# AnalogOutput.net
KiCad netlist of a schematic drawn in Altium Designer
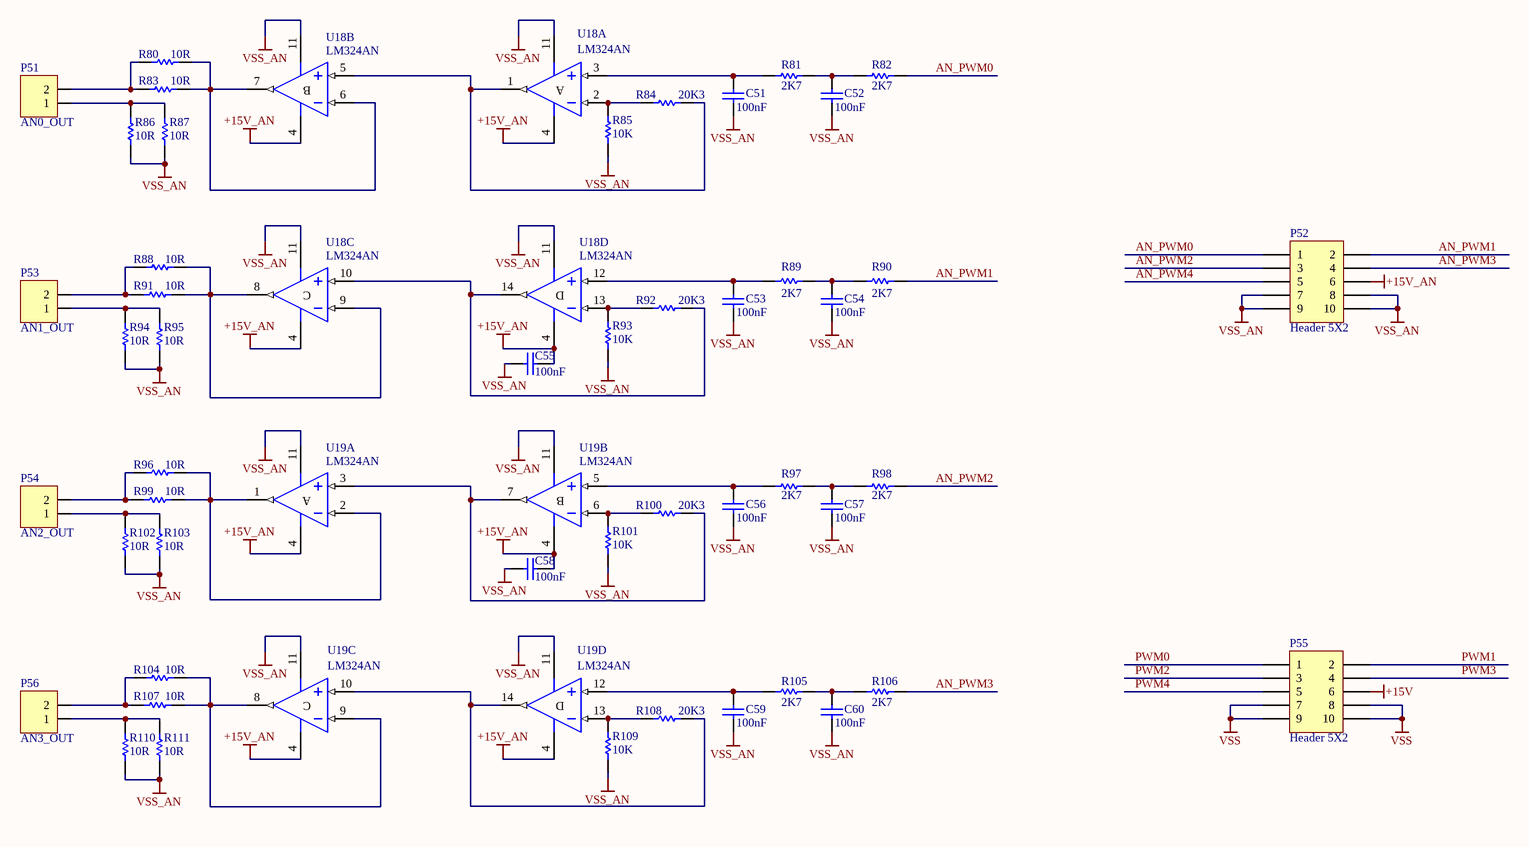
[diagram p0: AnalogOutput.SchDoc]

(export (version "E")
  (design (tool "Eeschema 10.0.6"))
  (components
    (comp (ref "C51")
      (value "100nF")
      (footprint "1206")
      (description "Ceramic Chip Capacitor - Standard")
      (fields (field (name "PUBLISHER") "Altium Limited"))
      (libsource (lib "KEMET Chip Capacitor") (part "C1206"))
    )
    (comp (ref "C52")
      (value "100nF")
      (footprint "1206")
      (description "Ceramic Chip Capacitor - Standard")
      (fields (field (name "PUBLISHER") "Altium Limited"))
      (libsource (lib "KEMET Chip Capacitor") (part "C1206"))
    )
    (comp (ref "C53")
      (value "100nF")
      (footprint "1206")
      (description "Ceramic Chip Capacitor - Standard")
      (fields (field (name "PUBLISHER") "Altium Limited"))
      (libsource (lib "KEMET Chip Capacitor") (part "C1206"))
    )
    (comp (ref "C54")
      (value "100nF")
      (footprint "1206")
      (description "Ceramic Chip Capacitor - Standard")
      (fields (field (name "PUBLISHER") "Altium Limited"))
      (libsource (lib "KEMET Chip Capacitor") (part "C1206"))
    )
    (comp (ref "C55")
      (value "100nF")
      (footprint "1206")
      (description "Ceramic Chip Capacitor - Standard")
      (fields (field (name "PUBLISHER") "Altium Limited"))
      (libsource (lib "KEMET Chip Capacitor") (part "C1206"))
    )
    (comp (ref "C56")
      (value "100nF")
      (footprint "1206")
      (description "Ceramic Chip Capacitor - Standard")
      (fields (field (name "PUBLISHER") "Altium Limited"))
      (libsource (lib "KEMET Chip Capacitor") (part "C1206"))
    )
    (comp (ref "C57")
      (value "100nF")
      (footprint "1206")
      (description "Ceramic Chip Capacitor - Standard")
      (fields (field (name "PUBLISHER") "Altium Limited"))
      (libsource (lib "KEMET Chip Capacitor") (part "C1206"))
    )
    (comp (ref "C58")
      (value "100nF")
      (footprint "1206")
      (description "Ceramic Chip Capacitor - Standard")
      (fields (field (name "PUBLISHER") "Altium Limited"))
      (libsource (lib "KEMET Chip Capacitor") (part "C1206"))
    )
    (comp (ref "C59")
      (value "100nF")
      (footprint "1206")
      (description "Ceramic Chip Capacitor - Standard")
      (fields (field (name "PUBLISHER") "Altium Limited"))
      (libsource (lib "KEMET Chip Capacitor") (part "C1206"))
    )
    (comp (ref "C60")
      (value "100nF")
      (footprint "1206")
      (description "Ceramic Chip Capacitor - Standard")
      (fields (field (name "PUBLISHER") "Altium Limited"))
      (libsource (lib "KEMET Chip Capacitor") (part "C1206"))
    )
    (comp (ref "P51")
      (value "AN0_OUT")
      (footprint "TERMINAL BLOK 2")
      (description "Terminal blok konektor 3,5 mm")
      (libsource (lib "ProjectLibrary") (part "TERMINAL BLOK 2"))
    )
    (comp (ref "P52")
      (value "Header 5X2")
      (footprint "HDR2X5")
      (description "Header, 5-Pin, Dual row")
      (fields (field (name "PUBLISHER") "Altium Limited"))
      (libsource (lib "Miscellaneous Connectors") (part "Header 5X2"))
    )
    (comp (ref "P53")
      (value "AN1_OUT")
      (footprint "TERMINAL BLOK 2")
      (description "Terminal blok konektor 3,5 mm")
      (libsource (lib "ProjectLibrary") (part "TERMINAL BLOK 2"))
    )
    (comp (ref "P54")
      (value "AN2_OUT")
      (footprint "TERMINAL BLOK 2")
      (description "Terminal blok konektor 3,5 mm")
      (libsource (lib "ProjectLibrary") (part "TERMINAL BLOK 2"))
    )
    (comp (ref "P55")
      (value "Header 5X2")
      (footprint "HDR2X5")
      (description "Header, 5-Pin, Dual row")
      (fields (field (name "PUBLISHER") "Altium Limited"))
      (libsource (lib "Miscellaneous Connectors") (part "Header 5X2"))
    )
    (comp (ref "P56")
      (value "AN3_OUT")
      (footprint "TERMINAL BLOK 2")
      (description "Terminal blok konektor 3,5 mm")
      (libsource (lib "ProjectLibrary") (part "TERMINAL BLOK 2"))
    )
    (comp (ref "R80")
      (value "10R")
      (footprint "ERA-0603")
      (fields (field (name "PUBLISHER") "Altium Limited"))
      (libsource (lib "Panasonic Resistor") (part "ERA3Y"))
    )
    (comp (ref "R81")
      (value "2K7")
      (footprint "ERA-0603")
      (fields (field (name "PUBLISHER") "Altium Limited"))
      (libsource (lib "Panasonic Resistor") (part "ERA3Y"))
    )
    (comp (ref "R82")
      (value "2K7")
      (footprint "ERA-0603")
      (fields (field (name "PUBLISHER") "Altium Limited"))
      (libsource (lib "Panasonic Resistor") (part "ERA3Y"))
    )
    (comp (ref "R83")
      (value "10R")
      (footprint "ERA-0603")
      (fields (field (name "PUBLISHER") "Altium Limited"))
      (libsource (lib "Panasonic Resistor") (part "ERA3Y"))
    )
    (comp (ref "R84")
      (value "20K3")
      (footprint "ERA-0603")
      (fields (field (name "PUBLISHER") "Altium Limited"))
      (libsource (lib "Panasonic Resistor") (part "ERA3Y"))
    )
    (comp (ref "R85")
      (value "10K")
      (footprint "ERA-0603")
      (fields (field (name "PUBLISHER") "Altium Limited"))
      (libsource (lib "Panasonic Resistor") (part "ERA3Y"))
    )
    (comp (ref "R86")
      (value "10R")
      (footprint "ERA-0603")
      (fields (field (name "PUBLISHER") "Altium Limited"))
      (libsource (lib "Panasonic Resistor") (part "ERA3Y"))
    )
    (comp (ref "R87")
      (value "10R")
      (footprint "ERA-0603")
      (fields (field (name "PUBLISHER") "Altium Limited"))
      (libsource (lib "Panasonic Resistor") (part "ERA3Y"))
    )
    (comp (ref "R88")
      (value "10R")
      (footprint "ERA-0603")
      (fields (field (name "PUBLISHER") "Altium Limited"))
      (libsource (lib "Panasonic Resistor") (part "ERA3Y"))
    )
    (comp (ref "R89")
      (value "2K7")
      (footprint "ERA-0603")
      (fields (field (name "PUBLISHER") "Altium Limited"))
      (libsource (lib "Panasonic Resistor") (part "ERA3Y"))
    )
    (comp (ref "R90")
      (value "2K7")
      (footprint "ERA-0603")
      (fields (field (name "PUBLISHER") "Altium Limited"))
      (libsource (lib "Panasonic Resistor") (part "ERA3Y"))
    )
    (comp (ref "R91")
      (value "10R")
      (footprint "ERA-0603")
      (fields (field (name "PUBLISHER") "Altium Limited"))
      (libsource (lib "Panasonic Resistor") (part "ERA3Y"))
    )
    (comp (ref "R92")
      (value "20K3")
      (footprint "ERA-0603")
      (fields (field (name "PUBLISHER") "Altium Limited"))
      (libsource (lib "Panasonic Resistor") (part "ERA3Y"))
    )
    (comp (ref "R93")
      (value "10K")
      (footprint "ERA-0603")
      (fields (field (name "PUBLISHER") "Altium Limited"))
      (libsource (lib "Panasonic Resistor") (part "ERA3Y"))
    )
    (comp (ref "R94")
      (value "10R")
      (footprint "ERA-0603")
      (fields (field (name "PUBLISHER") "Altium Limited"))
      (libsource (lib "Panasonic Resistor") (part "ERA3Y"))
    )
    (comp (ref "R95")
      (value "10R")
      (footprint "ERA-0603")
      (fields (field (name "PUBLISHER") "Altium Limited"))
      (libsource (lib "Panasonic Resistor") (part "ERA3Y"))
    )
    (comp (ref "R96")
      (value "10R")
      (footprint "ERA-0603")
      (fields (field (name "PUBLISHER") "Altium Limited"))
      (libsource (lib "Panasonic Resistor") (part "ERA3Y"))
    )
    (comp (ref "R97")
      (value "2K7")
      (footprint "ERA-0603")
      (fields (field (name "PUBLISHER") "Altium Limited"))
      (libsource (lib "Panasonic Resistor") (part "ERA3Y"))
    )
    (comp (ref "R98")
      (value "2K7")
      (footprint "ERA-0603")
      (fields (field (name "PUBLISHER") "Altium Limited"))
      (libsource (lib "Panasonic Resistor") (part "ERA3Y"))
    )
    (comp (ref "R99")
      (value "10R")
      (footprint "ERA-0603")
      (fields (field (name "PUBLISHER") "Altium Limited"))
      (libsource (lib "Panasonic Resistor") (part "ERA3Y"))
    )
    (comp (ref "R100")
      (value "20K3")
      (footprint "ERA-0603")
      (fields (field (name "PUBLISHER") "Altium Limited"))
      (libsource (lib "Panasonic Resistor") (part "ERA3Y"))
    )
    (comp (ref "R101")
      (value "10K")
      (footprint "ERA-0603")
      (fields (field (name "PUBLISHER") "Altium Limited"))
      (libsource (lib "Panasonic Resistor") (part "ERA3Y"))
    )
    (comp (ref "R102")
      (value "10R")
      (footprint "ERA-0603")
      (fields (field (name "PUBLISHER") "Altium Limited"))
      (libsource (lib "Panasonic Resistor") (part "ERA3Y"))
    )
    (comp (ref "R103")
      (value "10R")
      (footprint "ERA-0603")
      (fields (field (name "PUBLISHER") "Altium Limited"))
      (libsource (lib "Panasonic Resistor") (part "ERA3Y"))
    )
    (comp (ref "R104")
      (value "10R")
      (footprint "ERA-0603")
      (fields (field (name "PUBLISHER") "Altium Limited"))
      (libsource (lib "Panasonic Resistor") (part "ERA3Y"))
    )
    (comp (ref "R105")
      (value "2K7")
      (footprint "ERA-0603")
      (fields (field (name "PUBLISHER") "Altium Limited"))
      (libsource (lib "Panasonic Resistor") (part "ERA3Y"))
    )
    (comp (ref "R106")
      (value "2K7")
      (footprint "ERA-0603")
      (fields (field (name "PUBLISHER") "Altium Limited"))
      (libsource (lib "Panasonic Resistor") (part "ERA3Y"))
    )
    (comp (ref "R107")
      (value "10R")
      (footprint "ERA-0603")
      (fields (field (name "PUBLISHER") "Altium Limited"))
      (libsource (lib "Panasonic Resistor") (part "ERA3Y"))
    )
    (comp (ref "R108")
      (value "20K3")
      (footprint "ERA-0603")
      (fields (field (name "PUBLISHER") "Altium Limited"))
      (libsource (lib "Panasonic Resistor") (part "ERA3Y"))
    )
    (comp (ref "R109")
      (value "10K")
      (footprint "ERA-0603")
      (fields (field (name "PUBLISHER") "Altium Limited"))
      (libsource (lib "Panasonic Resistor") (part "ERA3Y"))
    )
    (comp (ref "R110")
      (value "10R")
      (footprint "ERA-0603")
      (fields (field (name "PUBLISHER") "Altium Limited"))
      (libsource (lib "Panasonic Resistor") (part "ERA3Y"))
    )
    (comp (ref "R111")
      (value "10R")
      (footprint "ERA-0603")
      (fields (field (name "PUBLISHER") "Altium Limited"))
      (libsource (lib "Panasonic Resistor") (part "ERA3Y"))
    )
    (comp (ref "U18")
      (value "LM324AN")
      (footprint "DIP14")
      (description "Low-Power Quad Operational Amplifier")
      (fields (field (name "PUBLISHER") "Altium Limited"))
      (libsource (lib "ST Operational Amplifier") (part "LM324AN"))
    )
    (comp (ref "U19")
      (value "LM324AN")
      (footprint "DIP14")
      (description "Low-Power Quad Operational Amplifier")
      (fields (field (name "PUBLISHER") "Altium Limited"))
      (libsource (lib "ST Operational Amplifier") (part "LM324AN"))
    )
  )
  (nets
    (net (code "1") (name "+15V") (class "Default")
      (node (ref "P55") (pin "6") (pinfunction "6_6") (pintype "passive"))
    )
    (net (code "2") (name "+15V_AN") (class "Default")
      (node (ref "C55") (pin "1") (pinfunction "1_1") (pintype "passive"))
      (node (ref "C58") (pin "1") (pinfunction "1_1") (pintype "passive"))
      (node (ref "P52") (pin "6") (pinfunction "6_6") (pintype "passive"))
      (node (ref "U18") (pin "4") (pinfunction "V+_4") (pintype "power_in"))
      (node (ref "U19") (pin "4") (pinfunction "V+_4") (pintype "power_in"))
    )
    (net (code "3") (name "/AN_PWM0") (class "Default")
      (node (ref "P52") (pin "1") (pinfunction "1_1") (pintype "passive"))
      (node (ref "R82") (pin "2") (pinfunction "2_2") (pintype "passive"))
    )
    (net (code "4") (name "/AN_PWM1") (class "Default")
      (node (ref "P52") (pin "2") (pinfunction "2_2") (pintype "passive"))
      (node (ref "R90") (pin "2") (pinfunction "2_2") (pintype "passive"))
    )
    (net (code "5") (name "/AN_PWM2") (class "Default")
      (node (ref "P52") (pin "3") (pinfunction "3_3") (pintype "passive"))
      (node (ref "R98") (pin "2") (pinfunction "2_2") (pintype "passive"))
    )
    (net (code "6") (name "/AN_PWM3") (class "Default")
      (node (ref "P52") (pin "4") (pinfunction "4_4") (pintype "passive"))
      (node (ref "R106") (pin "2") (pinfunction "2_2") (pintype "passive"))
    )
    (net (code "7") (name "/AN_PWM4") (class "Default")
      (node (ref "P52") (pin "5") (pinfunction "5_5") (pintype "passive"))
    )
    (net (code "8") (name "/PWM0") (class "Default")
      (node (ref "P55") (pin "1") (pinfunction "1_1") (pintype "passive"))
    )
    (net (code "9") (name "/PWM1") (class "Default")
      (node (ref "P55") (pin "2") (pinfunction "2_2") (pintype "passive"))
    )
    (net (code "10") (name "/PWM2") (class "Default")
      (node (ref "P55") (pin "3") (pinfunction "3_3") (pintype "passive"))
    )
    (net (code "11") (name "/PWM3") (class "Default")
      (node (ref "P55") (pin "4") (pinfunction "4_4") (pintype "passive"))
    )
    (net (code "12") (name "/PWM4") (class "Default")
      (node (ref "P55") (pin "5") (pinfunction "5_5") (pintype "passive"))
    )
    (net (code "13") (name "Net-(C52-Pad2)") (class "Default")
      (node (ref "C52") (pin "2") (pinfunction "2_2") (pintype "passive"))
      (node (ref "R81") (pin "2") (pinfunction "2_2") (pintype "passive"))
      (node (ref "R82") (pin "1") (pinfunction "1_1") (pintype "passive"))
    )
    (net (code "14") (name "Net-(C54-Pad2)") (class "Default")
      (node (ref "C54") (pin "2") (pinfunction "2_2") (pintype "passive"))
      (node (ref "R89") (pin "2") (pinfunction "2_2") (pintype "passive"))
      (node (ref "R90") (pin "1") (pinfunction "1_1") (pintype "passive"))
    )
    (net (code "15") (name "Net-(C57-Pad2)") (class "Default")
      (node (ref "C57") (pin "2") (pinfunction "2_2") (pintype "passive"))
      (node (ref "R97") (pin "2") (pinfunction "2_2") (pintype "passive"))
      (node (ref "R98") (pin "1") (pinfunction "1_1") (pintype "passive"))
    )
    (net (code "16") (name "Net-(C60-Pad2)") (class "Default")
      (node (ref "C60") (pin "2") (pinfunction "2_2") (pintype "passive"))
      (node (ref "R105") (pin "2") (pinfunction "2_2") (pintype "passive"))
      (node (ref "R106") (pin "1") (pinfunction "1_1") (pintype "passive"))
    )
    (net (code "17") (name "Net-(P51-Pad1)") (class "Default")
      (node (ref "P51") (pin "1") (pinfunction "1_1") (pintype "passive"))
      (node (ref "R86") (pin "2") (pinfunction "2_2") (pintype "passive"))
      (node (ref "R87") (pin "2") (pinfunction "2_2") (pintype "passive"))
    )
    (net (code "18") (name "Net-(P51-Pad2)") (class "Default")
      (node (ref "P51") (pin "2") (pinfunction "2_2") (pintype "passive"))
      (node (ref "R80") (pin "2") (pinfunction "2_2") (pintype "passive"))
      (node (ref "R83") (pin "2") (pinfunction "2_2") (pintype "passive"))
    )
    (net (code "19") (name "Net-(P53-Pad1)") (class "Default")
      (node (ref "P53") (pin "1") (pinfunction "1_1") (pintype "passive"))
      (node (ref "R94") (pin "2") (pinfunction "2_2") (pintype "passive"))
      (node (ref "R95") (pin "2") (pinfunction "2_2") (pintype "passive"))
    )
    (net (code "20") (name "Net-(P53-Pad2)") (class "Default")
      (node (ref "P53") (pin "2") (pinfunction "2_2") (pintype "passive"))
      (node (ref "R88") (pin "2") (pinfunction "2_2") (pintype "passive"))
      (node (ref "R91") (pin "2") (pinfunction "2_2") (pintype "passive"))
    )
    (net (code "21") (name "Net-(P54-Pad1)") (class "Default")
      (node (ref "P54") (pin "1") (pinfunction "1_1") (pintype "passive"))
      (node (ref "R102") (pin "2") (pinfunction "2_2") (pintype "passive"))
      (node (ref "R103") (pin "2") (pinfunction "2_2") (pintype "passive"))
    )
    (net (code "22") (name "Net-(P54-Pad2)") (class "Default")
      (node (ref "P54") (pin "2") (pinfunction "2_2") (pintype "passive"))
      (node (ref "R96") (pin "2") (pinfunction "2_2") (pintype "passive"))
      (node (ref "R99") (pin "2") (pinfunction "2_2") (pintype "passive"))
    )
    (net (code "23") (name "Net-(P56-Pad1)") (class "Default")
      (node (ref "P56") (pin "1") (pinfunction "1_1") (pintype "passive"))
      (node (ref "R110") (pin "2") (pinfunction "2_2") (pintype "passive"))
      (node (ref "R111") (pin "2") (pinfunction "2_2") (pintype "passive"))
    )
    (net (code "24") (name "Net-(P56-Pad2)") (class "Default")
      (node (ref "P56") (pin "2") (pinfunction "2_2") (pintype "passive"))
      (node (ref "R104") (pin "2") (pinfunction "2_2") (pintype "passive"))
      (node (ref "R107") (pin "2") (pinfunction "2_2") (pintype "passive"))
    )
    (net (code "25") (name "Net-(U18A-IN+)") (class "Default")
      (node (ref "C51") (pin "2") (pinfunction "2_2") (pintype "passive"))
      (node (ref "R81") (pin "1") (pinfunction "1_1") (pintype "passive"))
      (node (ref "U18") (pin "3") (pinfunction "IN+_3") (pintype "input"))
    )
    (net (code "26") (name "Net-(U18A-IN-)") (class "Default")
      (node (ref "R84") (pin "1") (pinfunction "1_1") (pintype "passive"))
      (node (ref "R85") (pin "2") (pinfunction "2_2") (pintype "passive"))
      (node (ref "U18") (pin "2") (pinfunction "IN-_2") (pintype "input"))
    )
    (net (code "27") (name "Net-(U18A-OUT)") (class "Default")
      (node (ref "R84") (pin "2") (pinfunction "2_2") (pintype "passive"))
      (node (ref "U18") (pin "1") (pinfunction "OUT_1") (pintype "output"))
      (node (ref "U18") (pin "5") (pinfunction "IN+_5") (pintype "input"))
    )
    (net (code "28") (name "Net-(U18B-IN-)") (class "Default")
      (node (ref "R80") (pin "1") (pinfunction "1_1") (pintype "passive"))
      (node (ref "R83") (pin "1") (pinfunction "1_1") (pintype "passive"))
      (node (ref "U18") (pin "6") (pinfunction "IN-_6") (pintype "input"))
      (node (ref "U18") (pin "7") (pinfunction "OUT_7") (pintype "output"))
    )
    (net (code "29") (name "Net-(U18C-IN+)") (class "Default")
      (node (ref "R92") (pin "2") (pinfunction "2_2") (pintype "passive"))
      (node (ref "U18") (pin "10") (pinfunction "IN+_10") (pintype "input"))
      (node (ref "U18") (pin "14") (pinfunction "OUT_14") (pintype "output"))
    )
    (net (code "30") (name "Net-(U18C-IN-)") (class "Default")
      (node (ref "R88") (pin "1") (pinfunction "1_1") (pintype "passive"))
      (node (ref "R91") (pin "1") (pinfunction "1_1") (pintype "passive"))
      (node (ref "U18") (pin "8") (pinfunction "OUT_8") (pintype "output"))
      (node (ref "U18") (pin "9") (pinfunction "IN-_9") (pintype "input"))
    )
    (net (code "31") (name "Net-(U18D-IN+)") (class "Default")
      (node (ref "C53") (pin "2") (pinfunction "2_2") (pintype "passive"))
      (node (ref "R89") (pin "1") (pinfunction "1_1") (pintype "passive"))
      (node (ref "U18") (pin "12") (pinfunction "IN+_12") (pintype "input"))
    )
    (net (code "32") (name "Net-(U18D-IN-)") (class "Default")
      (node (ref "R92") (pin "1") (pinfunction "1_1") (pintype "passive"))
      (node (ref "R93") (pin "2") (pinfunction "2_2") (pintype "passive"))
      (node (ref "U18") (pin "13") (pinfunction "IN-_13") (pintype "input"))
    )
    (net (code "33") (name "Net-(U19A-IN+)") (class "Default")
      (node (ref "R100") (pin "2") (pinfunction "2_2") (pintype "passive"))
      (node (ref "U19") (pin "3") (pinfunction "IN+_3") (pintype "input"))
      (node (ref "U19") (pin "7") (pinfunction "OUT_7") (pintype "output"))
    )
    (net (code "34") (name "Net-(U19A-IN-)") (class "Default")
      (node (ref "R96") (pin "1") (pinfunction "1_1") (pintype "passive"))
      (node (ref "R99") (pin "1") (pinfunction "1_1") (pintype "passive"))
      (node (ref "U19") (pin "1") (pinfunction "OUT_1") (pintype "output"))
      (node (ref "U19") (pin "2") (pinfunction "IN-_2") (pintype "input"))
    )
    (net (code "35") (name "Net-(U19B-IN+)") (class "Default")
      (node (ref "C56") (pin "2") (pinfunction "2_2") (pintype "passive"))
      (node (ref "R97") (pin "1") (pinfunction "1_1") (pintype "passive"))
      (node (ref "U19") (pin "5") (pinfunction "IN+_5") (pintype "input"))
    )
    (net (code "36") (name "Net-(U19B-IN-)") (class "Default")
      (node (ref "R100") (pin "1") (pinfunction "1_1") (pintype "passive"))
      (node (ref "R101") (pin "2") (pinfunction "2_2") (pintype "passive"))
      (node (ref "U19") (pin "6") (pinfunction "IN-_6") (pintype "input"))
    )
    (net (code "37") (name "Net-(U19C-IN+)") (class "Default")
      (node (ref "R108") (pin "2") (pinfunction "2_2") (pintype "passive"))
      (node (ref "U19") (pin "10") (pinfunction "IN+_10") (pintype "input"))
      (node (ref "U19") (pin "14") (pinfunction "OUT_14") (pintype "output"))
    )
    (net (code "38") (name "Net-(U19C-IN-)") (class "Default")
      (node (ref "R104") (pin "1") (pinfunction "1_1") (pintype "passive"))
      (node (ref "R107") (pin "1") (pinfunction "1_1") (pintype "passive"))
      (node (ref "U19") (pin "8") (pinfunction "OUT_8") (pintype "output"))
      (node (ref "U19") (pin "9") (pinfunction "IN-_9") (pintype "input"))
    )
    (net (code "39") (name "Net-(U19D-IN+)") (class "Default")
      (node (ref "C59") (pin "2") (pinfunction "2_2") (pintype "passive"))
      (node (ref "R105") (pin "1") (pinfunction "1_1") (pintype "passive"))
      (node (ref "U19") (pin "12") (pinfunction "IN+_12") (pintype "input"))
    )
    (net (code "40") (name "Net-(U19D-IN-)") (class "Default")
      (node (ref "R108") (pin "1") (pinfunction "1_1") (pintype "passive"))
      (node (ref "R109") (pin "2") (pinfunction "2_2") (pintype "passive"))
      (node (ref "U19") (pin "13") (pinfunction "IN-_13") (pintype "input"))
    )
    (net (code "41") (name "VSS") (class "Default")
      (node (ref "P55") (pin "10") (pinfunction "10_10") (pintype "passive"))
      (node (ref "P55") (pin "7") (pinfunction "7_7") (pintype "passive"))
      (node (ref "P55") (pin "8") (pinfunction "8_8") (pintype "passive"))
      (node (ref "P55") (pin "9") (pinfunction "9_9") (pintype "passive"))
    )
    (net (code "42") (name "VSS_AN") (class "Default")
      (node (ref "C51") (pin "1") (pinfunction "1_1") (pintype "passive"))
      (node (ref "C52") (pin "1") (pinfunction "1_1") (pintype "passive"))
      (node (ref "C53") (pin "1") (pinfunction "1_1") (pintype "passive"))
      (node (ref "C54") (pin "1") (pinfunction "1_1") (pintype "passive"))
      (node (ref "C55") (pin "2") (pinfunction "2_2") (pintype "passive"))
      (node (ref "C56") (pin "1") (pinfunction "1_1") (pintype "passive"))
      (node (ref "C57") (pin "1") (pinfunction "1_1") (pintype "passive"))
      (node (ref "C58") (pin "2") (pinfunction "2_2") (pintype "passive"))
      (node (ref "C59") (pin "1") (pinfunction "1_1") (pintype "passive"))
      (node (ref "C60") (pin "1") (pinfunction "1_1") (pintype "passive"))
      (node (ref "P52") (pin "10") (pinfunction "10_10") (pintype "passive"))
      (node (ref "P52") (pin "7") (pinfunction "7_7") (pintype "passive"))
      (node (ref "P52") (pin "8") (pinfunction "8_8") (pintype "passive"))
      (node (ref "P52") (pin "9") (pinfunction "9_9") (pintype "passive"))
      (node (ref "R101") (pin "1") (pinfunction "1_1") (pintype "passive"))
      (node (ref "R102") (pin "1") (pinfunction "1_1") (pintype "passive"))
      (node (ref "R103") (pin "1") (pinfunction "1_1") (pintype "passive"))
      (node (ref "R109") (pin "1") (pinfunction "1_1") (pintype "passive"))
      (node (ref "R110") (pin "1") (pinfunction "1_1") (pintype "passive"))
      (node (ref "R111") (pin "1") (pinfunction "1_1") (pintype "passive"))
      (node (ref "R85") (pin "1") (pinfunction "1_1") (pintype "passive"))
      (node (ref "R86") (pin "1") (pinfunction "1_1") (pintype "passive"))
      (node (ref "R87") (pin "1") (pinfunction "1_1") (pintype "passive"))
      (node (ref "R93") (pin "1") (pinfunction "1_1") (pintype "passive"))
      (node (ref "R94") (pin "1") (pinfunction "1_1") (pintype "passive"))
      (node (ref "R95") (pin "1") (pinfunction "1_1") (pintype "passive"))
      (node (ref "U18") (pin "11") (pinfunction "V-_11") (pintype "power_in"))
      (node (ref "U19") (pin "11") (pinfunction "V-_11") (pintype "power_in"))
    )
  )
)
